# Astavel_and_Monostable_Clock_Circuit_-_1.net
KiCad netlist of a schematic drawn in Altium Designer
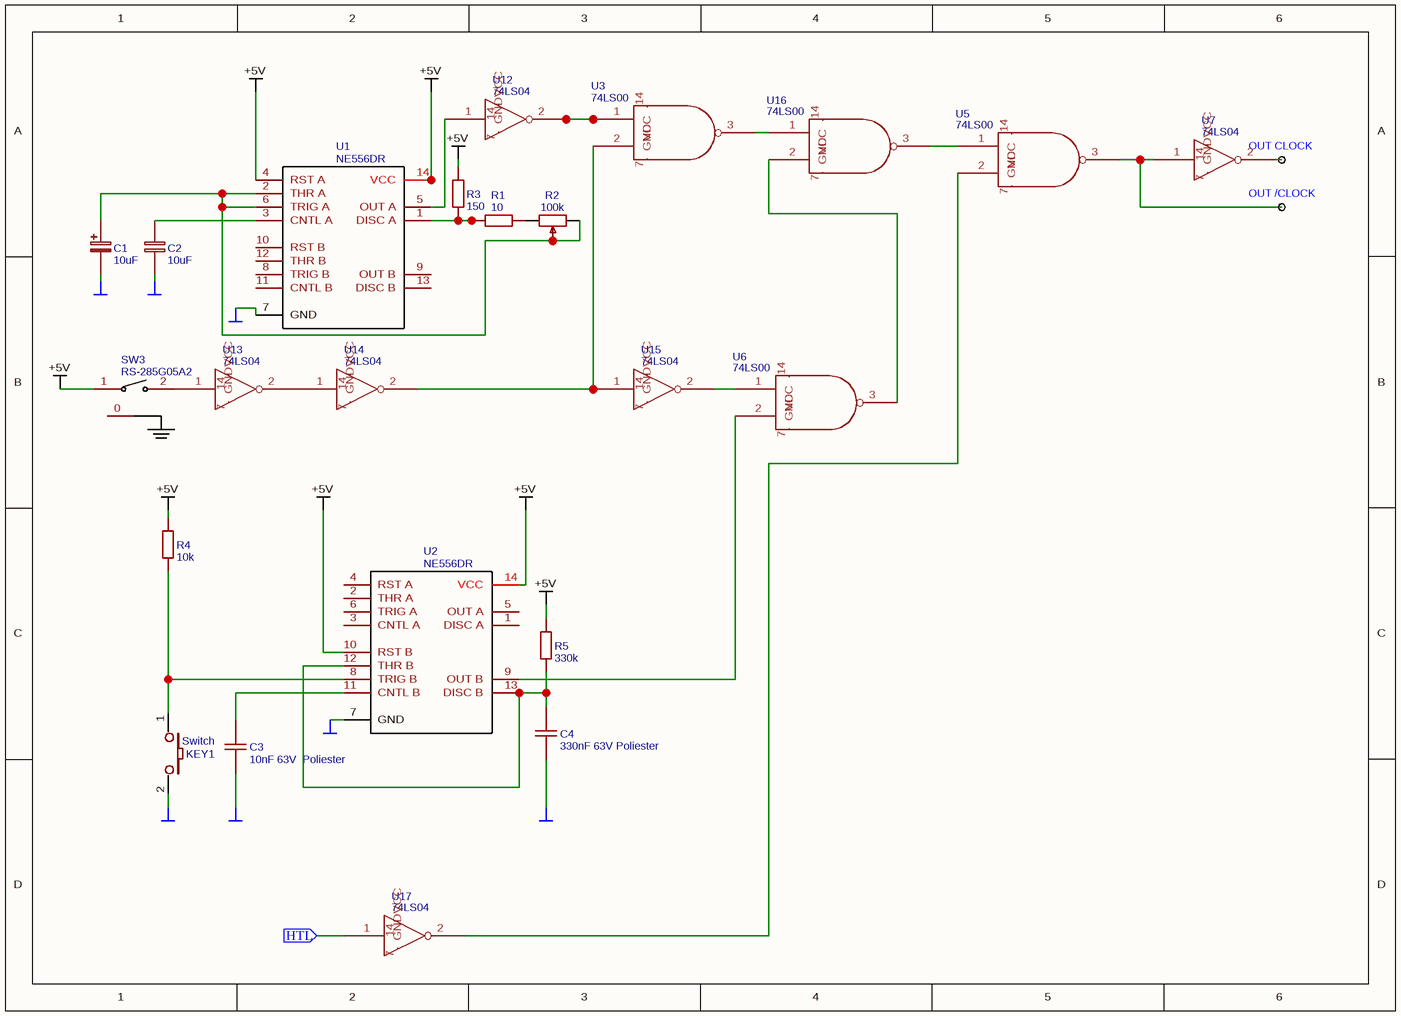
[diagram p0: Astavel and Monostable Clock Circuit - 1.0V_2021-10-04.schdoc]

(export (version "E")
  (design (tool "Eeschema 10.0.6"))
  (components
    (comp (ref "C1")
      (value "10uF")
      (fields (field (name "BOM_MANUFACTURER PART") "?") (field (name "CONTRIBUTOR") "EasyEDA"))
      (libsource (lib "altium-import") (part "root_0_10uF_"))
    )
    (comp (ref "C2")
      (value "10uF")
      (fields (field (name "BOM_MANUFACTURER PART") "?"))
      (libsource (lib "") (part "root_0_10uF__1"))
    )
    (comp (ref "C3")
      (value "10nF 63V  Poliester")
      (fields (field (name "BOM_MANUFACTURER PART") "?"))
      (libsource (lib "altium-import") (part "root_0_10nF 63V  Poliester_"))
    )
    (comp (ref "C4")
      (value "330nF 63V Poliester")
      (fields (field (name "BOM_MANUFACTURER PART") "?"))
      (libsource (lib "altium-import") (part "root_0_330nF 63V Poliester_"))
    )
    (comp (ref "KEY1")
      (value "Switch")
      (fields
        (field (name "BOM_MANUFACTURER PART") "Switch3x4x2")
        (field (name "BOM_SUPPLIER PART") "C26638")
        (field (name "CONTRIBUTOR") "LCSC")
      )
      (libsource (lib "altium-import") (part "root_3_Switch_"))
    )
    (comp (ref "R1")
      (value "10")
      (fields (field (name "BOM_MANUFACTURER PART") "?"))
      (libsource (lib "altium-import") (part "root_0_10_"))
    )
    (comp (ref "R2")
      (value "100k")
      (fields
        (field (name "BOM_SUPPLIER PART") "C125022")
        (field (name "BOM_MANUFACTURER PART") "3386P-1-101LF")
      )
      (libsource (lib "altium-import") (part "root_2_100k_"))
    )
    (comp (ref "R3")
      (value "150")
      (fields (field (name "BOM_MANUFACTURER PART") "?"))
      (libsource (lib "altium-import") (part "root_3_150_"))
    )
    (comp (ref "R4")
      (value "10k")
      (fields (field (name "BOM_MANUFACTURER PART") "?"))
      (libsource (lib "altium-import") (part "root_3_10k_"))
    )
    (comp (ref "R5")
      (value "330k")
      (fields (field (name "BOM_MANUFACTURER PART") "?"))
      (libsource (lib "altium-import") (part "root_3_330k_"))
    )
    (comp (ref "SW3")
      (value "RS-285G05A2")
      (fields
        (field (name "BOM_SUPPLIER PART") "C221931")
        (field (name "BOM_MANUFACTURER PART") "RS-285G05A2-URT")
        (field (name "CONTRIBUTOR") "LCSC")
      )
      (libsource (lib "altium-import") (part "root_0_RS-285G05A2_"))
    )
    (comp (ref "U1")
      (value "NE556DR")
      (fields (field (name "BOM_SUPPLIER PART") "C7427") (field (name "CONTRIBUTOR") "LCSC"))
      (libsource (lib "altium-import") (part "root_0_NE556DR_"))
    )
    (comp (ref "U2")
      (value "NE556DR")
      (fields (field (name "BOM_SUPPLIER PART") "C7427") (field (name "CONTRIBUTOR") "LCSC"))
      (libsource (lib "altium-import") (part "root_0_NE556DR_"))
    )
    (comp (ref "U3")
      (value "74LS00")
      (fields (field (name "BOM_MANUFACTURER PART") "?") (field (name "CONTRIBUTOR") "KiCad"))
      (libsource (lib "altium-import") (part "root_0_74LS00_"))
    )
    (comp (ref "U5")
      (value "74LS00")
      (fields (field (name "BOM_MANUFACTURER PART") "?") (field (name "CONTRIBUTOR") "KiCad"))
      (libsource (lib "altium-import") (part "root_0_74LS00_"))
    )
    (comp (ref "U6")
      (value "74LS00")
      (fields (field (name "BOM_MANUFACTURER PART") "?") (field (name "CONTRIBUTOR") "KiCad"))
      (libsource (lib "altium-import") (part "root_0_74LS00_"))
    )
    (comp (ref "U7")
      (value "74LS04")
      (fields (field (name "BOM_MANUFACTURER PART") "?") (field (name "CONTRIBUTOR") "KiCad"))
      (libsource (lib "altium-import") (part "root_0_74LS04_"))
    )
    (comp (ref "U12")
      (value "74LS04")
      (fields (field (name "BOM_MANUFACTURER PART") "?") (field (name "CONTRIBUTOR") "KiCad"))
      (libsource (lib "altium-import") (part "root_0_74LS04_"))
    )
    (comp (ref "U13")
      (value "74LS04")
      (fields (field (name "BOM_MANUFACTURER PART") "?") (field (name "CONTRIBUTOR") "KiCad"))
      (libsource (lib "altium-import") (part "root_0_74LS04_"))
    )
    (comp (ref "U14")
      (value "74LS04")
      (fields (field (name "BOM_MANUFACTURER PART") "?") (field (name "CONTRIBUTOR") "KiCad"))
      (libsource (lib "altium-import") (part "root_0_74LS04_"))
    )
    (comp (ref "U15")
      (value "74LS04")
      (fields (field (name "BOM_MANUFACTURER PART") "?") (field (name "CONTRIBUTOR") "KiCad"))
      (libsource (lib "altium-import") (part "root_0_74LS04_"))
    )
    (comp (ref "U16")
      (value "74LS00")
      (fields (field (name "BOM_MANUFACTURER PART") "?") (field (name "CONTRIBUTOR") "KiCad"))
      (libsource (lib "altium-import") (part "root_0_74LS00_"))
    )
    (comp (ref "U17")
      (value "74LS04")
      (fields (field (name "BOM_MANUFACTURER PART") "?") (field (name "CONTRIBUTOR") "KiCad"))
      (libsource (lib "altium-import") (part "root_0_74LS04_"))
    )
  )
  (nets
    (net (code "1") (name "+5V") (class "Default")
      (node (ref "R3") (pin "1") (pinfunction "1_1") (pintype "passive"))
      (node (ref "R4") (pin "1") (pinfunction "1_1") (pintype "passive"))
      (node (ref "R5") (pin "1") (pinfunction "1_1") (pintype "passive"))
      (node (ref "SW3") (pin "1") (pinfunction "1_1") (pintype "passive"))
      (node (ref "U1") (pin "14") (pinfunction "VCC_14") (pintype "passive"))
      (node (ref "U1") (pin "4") (pinfunction "RST_A_4") (pintype "passive"))
      (node (ref "U2") (pin "10") (pinfunction "RST_B_10") (pintype "passive"))
      (node (ref "U2") (pin "14") (pinfunction "VCC_14") (pintype "passive"))
    )
    (net (code "2") (name "/HTL") (class "Default")
      (node (ref "U17") (pin "1") (pinfunction "1_1") (pintype "passive"))
    )
    (net (code "3") (name "GND") (class "Default")
      (node (ref "C1") (pin "2") (pinfunction "2_2") (pintype "passive"))
      (node (ref "C2") (pin "2") (pinfunction "2_2") (pintype "passive"))
      (node (ref "C3") (pin "1") (pinfunction "1_1") (pintype "passive"))
      (node (ref "C4") (pin "1") (pinfunction "1_1") (pintype "passive"))
      (node (ref "KEY1") (pin "2") (pinfunction "2_2") (pintype "passive"))
      (node (ref "U1") (pin "7") (pinfunction "GND_7") (pintype "passive"))
      (node (ref "U2") (pin "7") (pinfunction "GND_7") (pintype "passive"))
    )
    (net (code "4") (name "Net-(R1-Pad2)") (class "Default")
      (node (ref "R1") (pin "2") (pinfunction "2_2") (pintype "passive"))
      (node (ref "R2") (pin "3") (pinfunction "3_3") (pintype "passive"))
    )
    (net (code "5") (name "Net-(SW3-Pad2)") (class "Default")
      (node (ref "SW3") (pin "2") (pinfunction "2_2") (pintype "passive"))
      (node (ref "U13") (pin "1") (pinfunction "1_1") (pintype "passive"))
    )
    (net (code "6") (name "Net-(U1-CNTL_A)") (class "Default")
      (node (ref "C2") (pin "1") (pinfunction "1_1") (pintype "passive"))
      (node (ref "U1") (pin "3") (pinfunction "CNTL_A_3") (pintype "passive"))
    )
    (net (code "7") (name "Net-(U1-DISC_A)") (class "Default")
      (node (ref "R1") (pin "1") (pinfunction "1_1") (pintype "passive"))
      (node (ref "R3") (pin "2") (pinfunction "2_2") (pintype "passive"))
      (node (ref "U1") (pin "1") (pinfunction "DISC_A_1") (pintype "passive"))
    )
    (net (code "8") (name "Net-(U1-OUT_A)") (class "Default")
      (node (ref "U1") (pin "5") (pinfunction "OUT_A_5") (pintype "passive"))
      (node (ref "U12") (pin "1") (pinfunction "1_1") (pintype "passive"))
    )
    (net (code "9") (name "Net-(U1-THR_A)") (class "Default")
      (node (ref "C1") (pin "1") (pinfunction "1_1") (pintype "passive"))
      (node (ref "R2") (pin "1") (pinfunction "1_1") (pintype "passive"))
      (node (ref "R2") (pin "2") (pinfunction "2_2") (pintype "passive"))
      (node (ref "U1") (pin "2") (pinfunction "THR_A_2") (pintype "passive"))
      (node (ref "U1") (pin "6") (pinfunction "TRIG_A_6") (pintype "passive"))
    )
    (net (code "10") (name "Net-(U2-CNTL_B)") (class "Default")
      (node (ref "C3") (pin "2") (pinfunction "2_2") (pintype "passive"))
      (node (ref "U2") (pin "11") (pinfunction "CNTL_B_11") (pintype "passive"))
    )
    (net (code "11") (name "Net-(U2-DISC_B)") (class "Default")
      (node (ref "C4") (pin "2") (pinfunction "2_2") (pintype "passive"))
      (node (ref "R5") (pin "2") (pinfunction "2_2") (pintype "passive"))
      (node (ref "U2") (pin "12") (pinfunction "THR_B_12") (pintype "passive"))
      (node (ref "U2") (pin "13") (pinfunction "DISC_B_13") (pintype "passive"))
    )
    (net (code "12") (name "Net-(U2-OUT_B)") (class "Default")
      (node (ref "U2") (pin "9") (pinfunction "OUT_B_9") (pintype "passive"))
      (node (ref "U6") (pin "2") (pinfunction "2_2") (pintype "passive"))
    )
    (net (code "13") (name "Net-(U2-TRIG_B)") (class "Default")
      (node (ref "KEY1") (pin "1") (pinfunction "1_1") (pintype "passive"))
      (node (ref "R4") (pin "2") (pinfunction "2_2") (pintype "passive"))
      (node (ref "U2") (pin "8") (pinfunction "TRIG_B_8") (pintype "passive"))
    )
    (net (code "14") (name "Net-(U5-Pad3)") (class "Default")
      (node (ref "U5") (pin "3") (pinfunction "3_3") (pintype "passive"))
      (node (ref "U7") (pin "1") (pinfunction "1_1") (pintype "passive"))
    )
    (net (code "15") (name "Net-(U12-Pad2)") (class "Default")
      (node (ref "U12") (pin "2") (pinfunction "2_2") (pintype "passive"))
      (node (ref "U3") (pin "1") (pinfunction "1_1") (pintype "passive"))
    )
    (net (code "16") (name "Net-(U13-Pad2)") (class "Default")
      (node (ref "U13") (pin "2") (pinfunction "2_2") (pintype "passive"))
      (node (ref "U14") (pin "1") (pinfunction "1_1") (pintype "passive"))
    )
    (net (code "17") (name "Net-(U14-Pad2)") (class "Default")
      (node (ref "U14") (pin "2") (pinfunction "2_2") (pintype "passive"))
      (node (ref "U15") (pin "1") (pinfunction "1_1") (pintype "passive"))
      (node (ref "U3") (pin "2") (pinfunction "2_2") (pintype "passive"))
    )
    (net (code "18") (name "Net-(U15-Pad2)") (class "Default")
      (node (ref "U15") (pin "2") (pinfunction "2_2") (pintype "passive"))
      (node (ref "U6") (pin "1") (pinfunction "1_1") (pintype "passive"))
    )
    (net (code "19") (name "Net-(U16-Pad1)") (class "Default")
      (node (ref "U16") (pin "1") (pinfunction "1_1") (pintype "passive"))
      (node (ref "U3") (pin "3") (pinfunction "3_3") (pintype "passive"))
    )
    (net (code "20") (name "Net-(U16-Pad2)") (class "Default")
      (node (ref "U16") (pin "2") (pinfunction "2_2") (pintype "passive"))
      (node (ref "U6") (pin "3") (pinfunction "3_3") (pintype "passive"))
    )
    (net (code "21") (name "Net-(U16-Pad3)") (class "Default")
      (node (ref "U16") (pin "3") (pinfunction "3_3") (pintype "passive"))
      (node (ref "U5") (pin "1") (pinfunction "1_1") (pintype "passive"))
    )
    (net (code "22") (name "Net-(U17-Pad2)") (class "Default")
      (node (ref "U17") (pin "2") (pinfunction "2_2") (pintype "passive"))
      (node (ref "U5") (pin "2") (pinfunction "2_2") (pintype "passive"))
    )
    (net (code "23") (name "unconnected-(SW3-Pad0)") (class "Default")
      (node (ref "SW3") (pin "0") (pinfunction "0_0") (pintype "passive"))
    )
    (net (code "24") (name "unconnected-(U1-CNTL_B-Pad11)") (class "Default")
      (node (ref "U1") (pin "11") (pinfunction "CNTL_B_11") (pintype "passive"))
    )
    (net (code "25") (name "unconnected-(U1-DISC_B-Pad13)") (class "Default")
      (node (ref "U1") (pin "13") (pinfunction "DISC_B_13") (pintype "passive"))
    )
    (net (code "26") (name "unconnected-(U1-OUT_B-Pad9)") (class "Default")
      (node (ref "U1") (pin "9") (pinfunction "OUT_B_9") (pintype "passive"))
    )
    (net (code "27") (name "unconnected-(U1-RST_B-Pad10)") (class "Default")
      (node (ref "U1") (pin "10") (pinfunction "RST_B_10") (pintype "passive"))
    )
    (net (code "28") (name "unconnected-(U1-THR_B-Pad12)") (class "Default")
      (node (ref "U1") (pin "12") (pinfunction "THR_B_12") (pintype "passive"))
    )
    (net (code "29") (name "unconnected-(U1-TRIG_B-Pad8)") (class "Default")
      (node (ref "U1") (pin "8") (pinfunction "TRIG_B_8") (pintype "passive"))
    )
    (net (code "30") (name "unconnected-(U2-CNTL_A-Pad3)") (class "Default")
      (node (ref "U2") (pin "3") (pinfunction "CNTL_A_3") (pintype "passive"))
    )
    (net (code "31") (name "unconnected-(U2-DISC_A-Pad1)") (class "Default")
      (node (ref "U2") (pin "1") (pinfunction "DISC_A_1") (pintype "passive"))
    )
    (net (code "32") (name "unconnected-(U2-OUT_A-Pad5)") (class "Default")
      (node (ref "U2") (pin "5") (pinfunction "OUT_A_5") (pintype "passive"))
    )
    (net (code "33") (name "unconnected-(U2-RST_A-Pad4)") (class "Default")
      (node (ref "U2") (pin "4") (pinfunction "RST_A_4") (pintype "passive"))
    )
    (net (code "34") (name "unconnected-(U2-THR_A-Pad2)") (class "Default")
      (node (ref "U2") (pin "2") (pinfunction "THR_A_2") (pintype "passive"))
    )
    (net (code "35") (name "unconnected-(U2-TRIG_A-Pad6)") (class "Default")
      (node (ref "U2") (pin "6") (pinfunction "TRIG_A_6") (pintype "passive"))
    )
    (net (code "36") (name "unconnected-(U3-GND-Pad7)") (class "Default")
      (node (ref "U3") (pin "7") (pinfunction "GND_7") (pintype "passive"))
    )
    (net (code "37") (name "unconnected-(U3-VCC-Pad14)") (class "Default")
      (node (ref "U3") (pin "14") (pinfunction "VCC_14") (pintype "passive"))
    )
    (net (code "38") (name "unconnected-(U5-GND-Pad7)") (class "Default")
      (node (ref "U5") (pin "7") (pinfunction "GND_7") (pintype "passive"))
    )
    (net (code "39") (name "unconnected-(U5-VCC-Pad14)") (class "Default")
      (node (ref "U5") (pin "14") (pinfunction "VCC_14") (pintype "passive"))
    )
    (net (code "40") (name "unconnected-(U6-GND-Pad7)") (class "Default")
      (node (ref "U6") (pin "7") (pinfunction "GND_7") (pintype "passive"))
    )
    (net (code "41") (name "unconnected-(U6-VCC-Pad14)") (class "Default")
      (node (ref "U6") (pin "14") (pinfunction "VCC_14") (pintype "passive"))
    )
    (net (code "42") (name "unconnected-(U7-GND-Pad7)") (class "Default")
      (node (ref "U7") (pin "7") (pinfunction "GND_7") (pintype "passive"))
    )
    (net (code "43") (name "unconnected-(U7-Pad2)") (class "Default")
      (node (ref "U7") (pin "2") (pinfunction "2_2") (pintype "passive"))
    )
    (net (code "44") (name "unconnected-(U7-VCC-Pad14)") (class "Default")
      (node (ref "U7") (pin "14") (pinfunction "VCC_14") (pintype "passive"))
    )
    (net (code "45") (name "unconnected-(U12-GND-Pad7)") (class "Default")
      (node (ref "U12") (pin "7") (pinfunction "GND_7") (pintype "passive"))
    )
    (net (code "46") (name "unconnected-(U12-VCC-Pad14)") (class "Default")
      (node (ref "U12") (pin "14") (pinfunction "VCC_14") (pintype "passive"))
    )
    (net (code "47") (name "unconnected-(U13-GND-Pad7)") (class "Default")
      (node (ref "U13") (pin "7") (pinfunction "GND_7") (pintype "passive"))
    )
    (net (code "48") (name "unconnected-(U13-VCC-Pad14)") (class "Default")
      (node (ref "U13") (pin "14") (pinfunction "VCC_14") (pintype "passive"))
    )
    (net (code "49") (name "unconnected-(U14-GND-Pad7)") (class "Default")
      (node (ref "U14") (pin "7") (pinfunction "GND_7") (pintype "passive"))
    )
    (net (code "50") (name "unconnected-(U14-VCC-Pad14)") (class "Default")
      (node (ref "U14") (pin "14") (pinfunction "VCC_14") (pintype "passive"))
    )
    (net (code "51") (name "unconnected-(U15-GND-Pad7)") (class "Default")
      (node (ref "U15") (pin "7") (pinfunction "GND_7") (pintype "passive"))
    )
    (net (code "52") (name "unconnected-(U15-VCC-Pad14)") (class "Default")
      (node (ref "U15") (pin "14") (pinfunction "VCC_14") (pintype "passive"))
    )
    (net (code "53") (name "unconnected-(U16-GND-Pad7)") (class "Default")
      (node (ref "U16") (pin "7") (pinfunction "GND_7") (pintype "passive"))
    )
    (net (code "54") (name "unconnected-(U16-VCC-Pad14)") (class "Default")
      (node (ref "U16") (pin "14") (pinfunction "VCC_14") (pintype "passive"))
    )
    (net (code "55") (name "unconnected-(U17-GND-Pad7)") (class "Default")
      (node (ref "U17") (pin "7") (pinfunction "GND_7") (pintype "passive"))
    )
    (net (code "56") (name "unconnected-(U17-VCC-Pad14)") (class "Default")
      (node (ref "U17") (pin "14") (pinfunction "VCC_14") (pintype "passive"))
    )
  )
)
